# kugavd.net
KiCad netlist of a schematic drawn in EAGLE
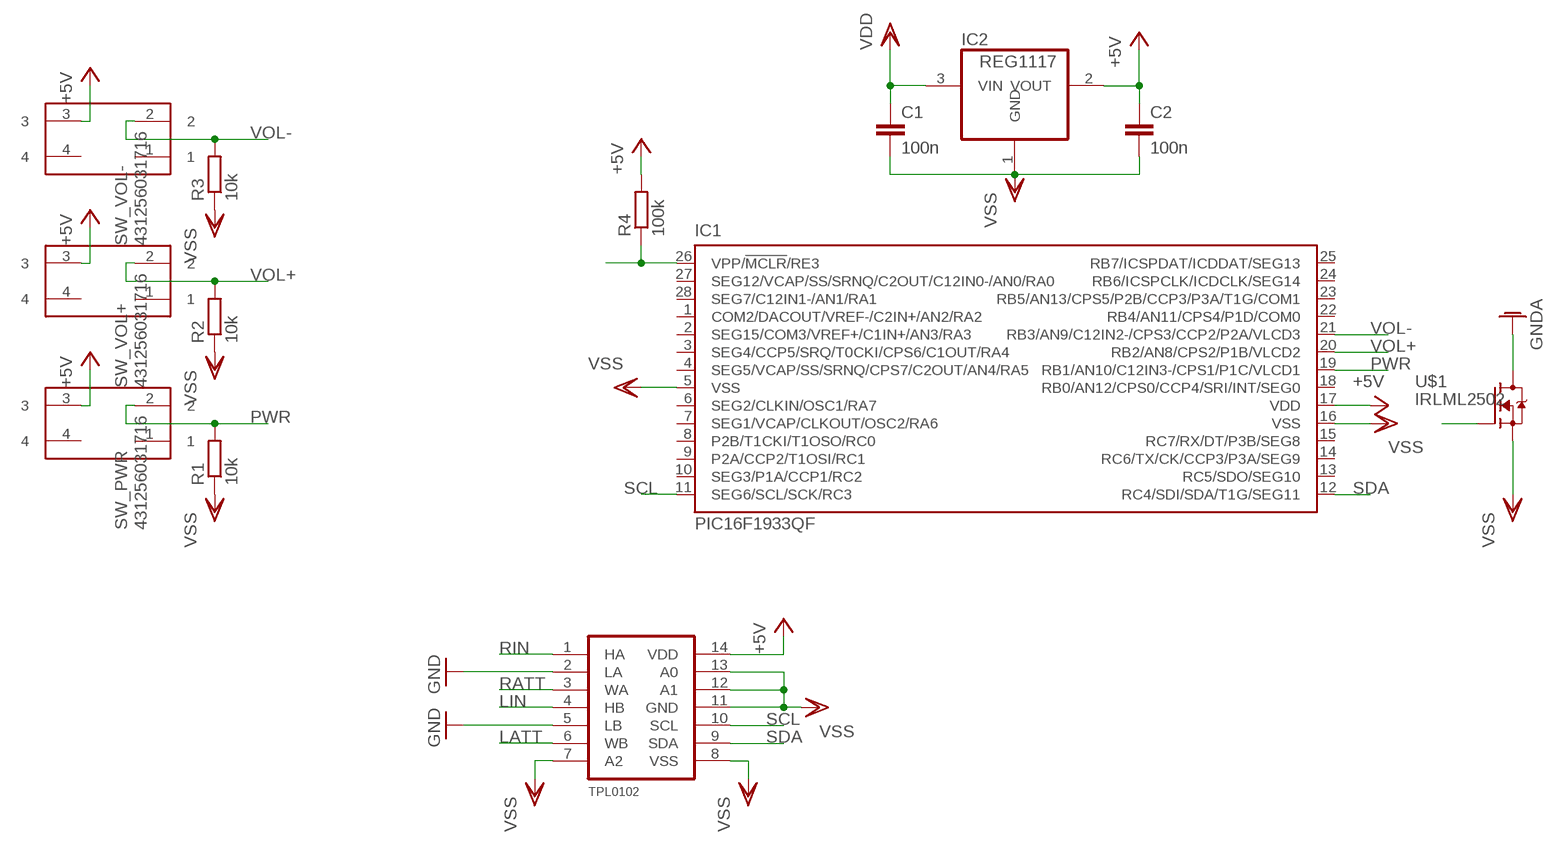
[diagram p0: schematic, sheet 1]

(export (version "E")
  (design (tool "Eeschema 10.0.6"))
  (components
    (comp (ref "C1")
      (value "100n")
      (footprint "eagle-import:C1206K")
      (libsource (lib "eagle-import") (part "C-EUC1206K"))
    )
    (comp (ref "C2")
      (value "100n")
      (footprint "eagle-import:C1206K")
      (libsource (lib "eagle-import") (part "C-EUC1206K"))
    )
    (comp (ref "IC1")
      (value "PIC16F1933QF")
      (footprint "eagle-import:QFN28-ML_6X6MM")
      (fields (field (name "MPN") "PIC16F1933-I/ML"))
      (libsource (lib "eagle-import") (part "PIC16F19QF33"))
    )
    (comp (ref "IC2")
      (value "REG1117")
      (footprint "eagle-import:SOT223")
      (libsource (lib "eagle-import") (part "REG1117"))
    )
    (comp (ref "R1")
      (value "10k")
      (footprint "eagle-import:R1206")
      (libsource (lib "eagle-import") (part "R-EU_R1206"))
    )
    (comp (ref "R2")
      (value "10k")
      (footprint "eagle-import:R1206")
      (libsource (lib "eagle-import") (part "R-EU_R1206"))
    )
    (comp (ref "R3")
      (value "10k")
      (footprint "eagle-import:R1206")
      (libsource (lib "eagle-import") (part "R-EU_R1206"))
    )
    (comp (ref "R4")
      (value "100k")
      (footprint "eagle-import:R1206")
      (libsource (lib "eagle-import") (part "R-EU_R1206"))
    )
    (comp (ref "SW_PWR")
      (value "431256031716")
      (footprint "eagle-import:431256031716")
      (libsource (lib "eagle-import") (part "431256031716"))
    )
    (comp (ref "SW_VOL+")
      (value "431256031716")
      (footprint "eagle-import:431256031716")
      (libsource (lib "eagle-import") (part "431256031716"))
    )
    (comp (ref "SW_VOL-")
      (value "431256031716")
      (footprint "eagle-import:431256031716")
      (libsource (lib "eagle-import") (part "431256031716"))
    )
    (comp (ref "TPL0102")
      (value "TPL0102")
      (footprint "eagle-import:TSSOP16L")
      (libsource (lib "eagle-import") (part "TPL0102"))
    )
    (comp (ref "U$1")
      (value "IRLML2502")
      (footprint "eagle-import:SOT23")
      (libsource (lib "eagle-import") (part "IRLML2502"))
    )
  )
  (nets
    (net (code "1") (name "+5V") (class "Default")
      (node (ref "C2") (pin "1") (pinfunction "1_1") (pintype "passive"))
      (node (ref "IC1") (pin "17") (pinfunction "VDD_17") (pintype "power_in"))
      (node (ref "IC2") (pin "2") (pinfunction "VOUT_2") (pintype "output"))
      (node (ref "R4") (pin "2") (pinfunction "2_2") (pintype "passive"))
      (node (ref "SW_PWR") (pin "3") (pinfunction "3_3") (pintype "bidirectional"))
      (node (ref "SW_VOL+") (pin "3") (pinfunction "3_3") (pintype "bidirectional"))
      (node (ref "SW_VOL-") (pin "3") (pinfunction "3_3") (pintype "bidirectional"))
      (node (ref "TPL0102") (pin "14") (pinfunction "VDD_14") (pintype "bidirectional"))
    )
    (net (code "2") (name "/LATT") (class "Default")
      (node (ref "TPL0102") (pin "6") (pinfunction "WB_6") (pintype "bidirectional"))
    )
    (net (code "3") (name "/LIN") (class "Default")
      (node (ref "TPL0102") (pin "4") (pinfunction "HB_4") (pintype "bidirectional"))
    )
    (net (code "4") (name "/PWR") (class "Default")
      (node (ref "IC1") (pin "19") (pinfunction "RB1/AN10/C12IN3-/CPS1/P1C/VLCD1_19") (pintype "bidirectional"))
      (node (ref "R1") (pin "2") (pinfunction "2_2") (pintype "passive"))
      (node (ref "SW_PWR") (pin "2") (pinfunction "2_2") (pintype "bidirectional"))
    )
    (net (code "5") (name "/RATT") (class "Default")
      (node (ref "TPL0102") (pin "3") (pinfunction "WA_3") (pintype "bidirectional"))
    )
    (net (code "6") (name "/RIN") (class "Default")
      (node (ref "TPL0102") (pin "1") (pinfunction "HA_1") (pintype "bidirectional"))
    )
    (net (code "7") (name "/SCL") (class "Default")
      (node (ref "IC1") (pin "11") (pinfunction "SEG6/SCL/SCK/RC3_11") (pintype "bidirectional"))
      (node (ref "TPL0102") (pin "10") (pinfunction "SCL_10") (pintype "bidirectional"))
    )
    (net (code "8") (name "/SDA") (class "Default")
      (node (ref "IC1") (pin "12") (pinfunction "RC4/SDI/SDA/T1G/SEG11_12") (pintype "bidirectional"))
      (node (ref "TPL0102") (pin "9") (pinfunction "SDA_9") (pintype "bidirectional"))
    )
    (net (code "9") (name "/VOL+") (class "Default")
      (node (ref "IC1") (pin "20") (pinfunction "RB2/AN8/CPS2/P1B/VLCD2_20") (pintype "bidirectional"))
      (node (ref "R2") (pin "2") (pinfunction "2_2") (pintype "passive"))
      (node (ref "SW_VOL+") (pin "2") (pinfunction "2_2") (pintype "bidirectional"))
    )
    (net (code "10") (name "/VOL-") (class "Default")
      (node (ref "IC1") (pin "21") (pinfunction "RB3/AN9/C12IN2-/CPS3/CCP2/P2A/VLCD3_21") (pintype "bidirectional"))
      (node (ref "R3") (pin "2") (pinfunction "2_2") (pintype "passive"))
      (node (ref "SW_VOL-") (pin "2") (pinfunction "2_2") (pintype "bidirectional"))
    )
    (net (code "11") (name "GND") (class "Default")
      (node (ref "TPL0102") (pin "2") (pinfunction "LA_2") (pintype "bidirectional"))
      (node (ref "TPL0102") (pin "5") (pinfunction "LB_5") (pintype "bidirectional"))
    )
    (net (code "12") (name "GNDA") (class "Default")
      (node (ref "U$1") (pin "3") (pinfunction "D_3") (pintype "passive"))
    )
    (net (code "13") (name "Net-(IC1-VPP{slash}~{MCLR}{slash}RE3)") (class "Default")
      (node (ref "IC1") (pin "26") (pinfunction "VPP/~{MCLR}/RE3_26") (pintype "input"))
      (node (ref "R4") (pin "1") (pinfunction "1_1") (pintype "passive"))
    )
    (net (code "14") (name "VDD") (class "Default")
      (node (ref "C1") (pin "1") (pinfunction "1_1") (pintype "passive"))
      (node (ref "IC2") (pin "3") (pinfunction "VIN_3") (pintype "input"))
    )
    (net (code "15") (name "VSS") (class "Default")
      (node (ref "C1") (pin "2") (pinfunction "2_2") (pintype "passive"))
      (node (ref "C2") (pin "2") (pinfunction "2_2") (pintype "passive"))
      (node (ref "IC1") (pin "16") (pinfunction "VSS_16") (pintype "power_in"))
      (node (ref "IC1") (pin "5") (pinfunction "VSS_5") (pintype "power_in"))
      (node (ref "IC2") (pin "1") (pinfunction "GND_1") (pintype "power_in"))
      (node (ref "R1") (pin "1") (pinfunction "1_1") (pintype "passive"))
      (node (ref "R2") (pin "1") (pinfunction "1_1") (pintype "passive"))
      (node (ref "R3") (pin "1") (pinfunction "1_1") (pintype "passive"))
      (node (ref "TPL0102") (pin "11") (pinfunction "GND_11") (pintype "bidirectional"))
      (node (ref "TPL0102") (pin "12") (pinfunction "A1_12") (pintype "bidirectional"))
      (node (ref "TPL0102") (pin "13") (pinfunction "A0_13") (pintype "bidirectional"))
      (node (ref "TPL0102") (pin "7") (pinfunction "A2_7") (pintype "bidirectional"))
      (node (ref "TPL0102") (pin "8") (pinfunction "VSS_8") (pintype "bidirectional"))
      (node (ref "U$1") (pin "2") (pinfunction "S_2") (pintype "passive"))
    )
    (net (code "16") (name "unconnected-(IC1-COM2{slash}DACOUT{slash}VREF-{slash}C2IN+{slash}AN2{slash}RA2-Pad1)") (class "Default")
      (node (ref "IC1") (pin "1") (pinfunction "COM2/DACOUT/VREF-/C2IN+/AN2/RA2_1") (pintype "bidirectional"))
    )
    (net (code "17") (name "unconnected-(IC1-P2A{slash}CCP2{slash}T1OSI{slash}RC1-Pad9)") (class "Default")
      (node (ref "IC1") (pin "9") (pinfunction "P2A/CCP2/T1OSI/RC1_9") (pintype "bidirectional"))
    )
    (net (code "18") (name "unconnected-(IC1-P2B{slash}T1CKI{slash}T1OSO{slash}RC0-Pad8)") (class "Default")
      (node (ref "IC1") (pin "8") (pinfunction "P2B/T1CKI/T1OSO/RC0_8") (pintype "bidirectional"))
    )
    (net (code "19") (name "unconnected-(IC1-RB0{slash}AN12{slash}CPS0{slash}CCP4{slash}SRI{slash}INT{slash}SEG0-Pad18)") (class "Default")
      (node (ref "IC1") (pin "18") (pinfunction "RB0/AN12/CPS0/CCP4/SRI/INT/SEG0_18") (pintype "bidirectional"))
    )
    (net (code "20") (name "unconnected-(IC1-RB4{slash}AN11{slash}CPS4{slash}P1D{slash}COM0-Pad22)") (class "Default")
      (node (ref "IC1") (pin "22") (pinfunction "RB4/AN11/CPS4/P1D/COM0_22") (pintype "bidirectional"))
    )
    (net (code "21") (name "unconnected-(IC1-RB5{slash}AN13{slash}CPS5{slash}P2B{slash}CCP3{slash}P3A{slash}T1G{slash}COM1-Pad23)") (class "Default")
      (node (ref "IC1") (pin "23") (pinfunction "RB5/AN13/CPS5/P2B/CCP3/P3A/T1G/COM1_23") (pintype "bidirectional"))
    )
    (net (code "22") (name "unconnected-(IC1-RB6{slash}ICSPCLK{slash}ICDCLK{slash}SEG14-Pad24)") (class "Default")
      (node (ref "IC1") (pin "24") (pinfunction "RB6/ICSPCLK/ICDCLK/SEG14_24") (pintype "bidirectional"))
    )
    (net (code "23") (name "unconnected-(IC1-RB7{slash}ICSPDAT{slash}ICDDAT{slash}SEG13-Pad25)") (class "Default")
      (node (ref "IC1") (pin "25") (pinfunction "RB7/ICSPDAT/ICDDAT/SEG13_25") (pintype "bidirectional"))
    )
    (net (code "24") (name "unconnected-(IC1-RC5{slash}SDO{slash}SEG10-Pad13)") (class "Default")
      (node (ref "IC1") (pin "13") (pinfunction "RC5/SDO/SEG10_13") (pintype "bidirectional"))
    )
    (net (code "25") (name "unconnected-(IC1-RC6{slash}TX{slash}CK{slash}CCP3{slash}P3A{slash}SEG9-Pad14)") (class "Default")
      (node (ref "IC1") (pin "14") (pinfunction "RC6/TX/CK/CCP3/P3A/SEG9_14") (pintype "bidirectional"))
    )
    (net (code "26") (name "unconnected-(IC1-RC7{slash}RX{slash}DT{slash}P3B{slash}SEG8-Pad15)") (class "Default")
      (node (ref "IC1") (pin "15") (pinfunction "RC7/RX/DT/P3B/SEG8_15") (pintype "bidirectional"))
    )
    (net (code "27") (name "unconnected-(IC1-SEG1{slash}VCAP{slash}CLKOUT{slash}OSC2{slash}RA6-Pad7)") (class "Default")
      (node (ref "IC1") (pin "7") (pinfunction "SEG1/VCAP/CLKOUT/OSC2/RA6_7") (pintype "bidirectional"))
    )
    (net (code "28") (name "unconnected-(IC1-SEG2{slash}CLKIN{slash}OSC1{slash}RA7-Pad6)") (class "Default")
      (node (ref "IC1") (pin "6") (pinfunction "SEG2/CLKIN/OSC1/RA7_6") (pintype "bidirectional"))
    )
    (net (code "29") (name "unconnected-(IC1-SEG3{slash}P1A{slash}CCP1{slash}RC2-Pad10)") (class "Default")
      (node (ref "IC1") (pin "10") (pinfunction "SEG3/P1A/CCP1/RC2_10") (pintype "bidirectional"))
    )
    (net (code "30") (name "unconnected-(IC1-SEG4{slash}CCP5{slash}SRQ{slash}T0CKI{slash}CPS6{slash}C1OUT{slash}RA4-Pad3)") (class "Default")
      (node (ref "IC1") (pin "3") (pinfunction "SEG4/CCP5/SRQ/T0CKI/CPS6/C1OUT/RA4_3") (pintype "bidirectional"))
    )
    (net (code "31") (name "unconnected-(IC1-SEG5{slash}VCAP{slash}SS{slash}SRNQ{slash}CPS7{slash}C2OUT{slash}AN4{slash}RA5-Pad4)") (class "Default")
      (node (ref "IC1") (pin "4") (pinfunction "SEG5/VCAP/SS/SRNQ/CPS7/C2OUT/AN4/RA5_4") (pintype "bidirectional"))
    )
    (net (code "32") (name "unconnected-(IC1-SEG7{slash}C12IN1-{slash}AN1{slash}RA1-Pad28)") (class "Default")
      (node (ref "IC1") (pin "28") (pinfunction "SEG7/C12IN1-/AN1/RA1_28") (pintype "bidirectional"))
    )
    (net (code "33") (name "unconnected-(IC1-SEG12{slash}VCAP{slash}SS{slash}SRNQ{slash}C2OUT{slash}C12IN0-{slash}AN0{slash}RA0-Pad27)") (class "Default")
      (node (ref "IC1") (pin "27") (pinfunction "SEG12/VCAP/SS/SRNQ/C2OUT/C12IN0-/AN0/RA0_27") (pintype "bidirectional"))
    )
    (net (code "34") (name "unconnected-(IC1-SEG15{slash}COM3{slash}VREF+{slash}C1IN+{slash}AN3{slash}RA3-Pad2)") (class "Default")
      (node (ref "IC1") (pin "2") (pinfunction "SEG15/COM3/VREF+/C1IN+/AN3/RA3_2") (pintype "bidirectional"))
    )
    (net (code "35") (name "unconnected-(SW_PWR-Pad1)") (class "Default")
      (node (ref "SW_PWR") (pin "1") (pinfunction "1_1") (pintype "bidirectional"))
    )
    (net (code "36") (name "unconnected-(SW_PWR-Pad4)") (class "Default")
      (node (ref "SW_PWR") (pin "4") (pinfunction "4_4") (pintype "bidirectional"))
    )
    (net (code "37") (name "unconnected-(SW_VOL+-Pad1)") (class "Default")
      (node (ref "SW_VOL+") (pin "1") (pinfunction "1_1") (pintype "bidirectional"))
    )
    (net (code "38") (name "unconnected-(SW_VOL+-Pad4)") (class "Default")
      (node (ref "SW_VOL+") (pin "4") (pinfunction "4_4") (pintype "bidirectional"))
    )
    (net (code "39") (name "unconnected-(SW_VOL--Pad1)") (class "Default")
      (node (ref "SW_VOL-") (pin "1") (pinfunction "1_1") (pintype "bidirectional"))
    )
    (net (code "40") (name "unconnected-(SW_VOL--Pad4)") (class "Default")
      (node (ref "SW_VOL-") (pin "4") (pinfunction "4_4") (pintype "bidirectional"))
    )
    (net (code "41") (name "unconnected-(U$1-G-Pad1)") (class "Default")
      (node (ref "U$1") (pin "1") (pinfunction "G_1") (pintype "passive"))
    )
  )
)
